# EtherCAT_Sheet.net
KiCad netlist of a schematic drawn in Altium Designer
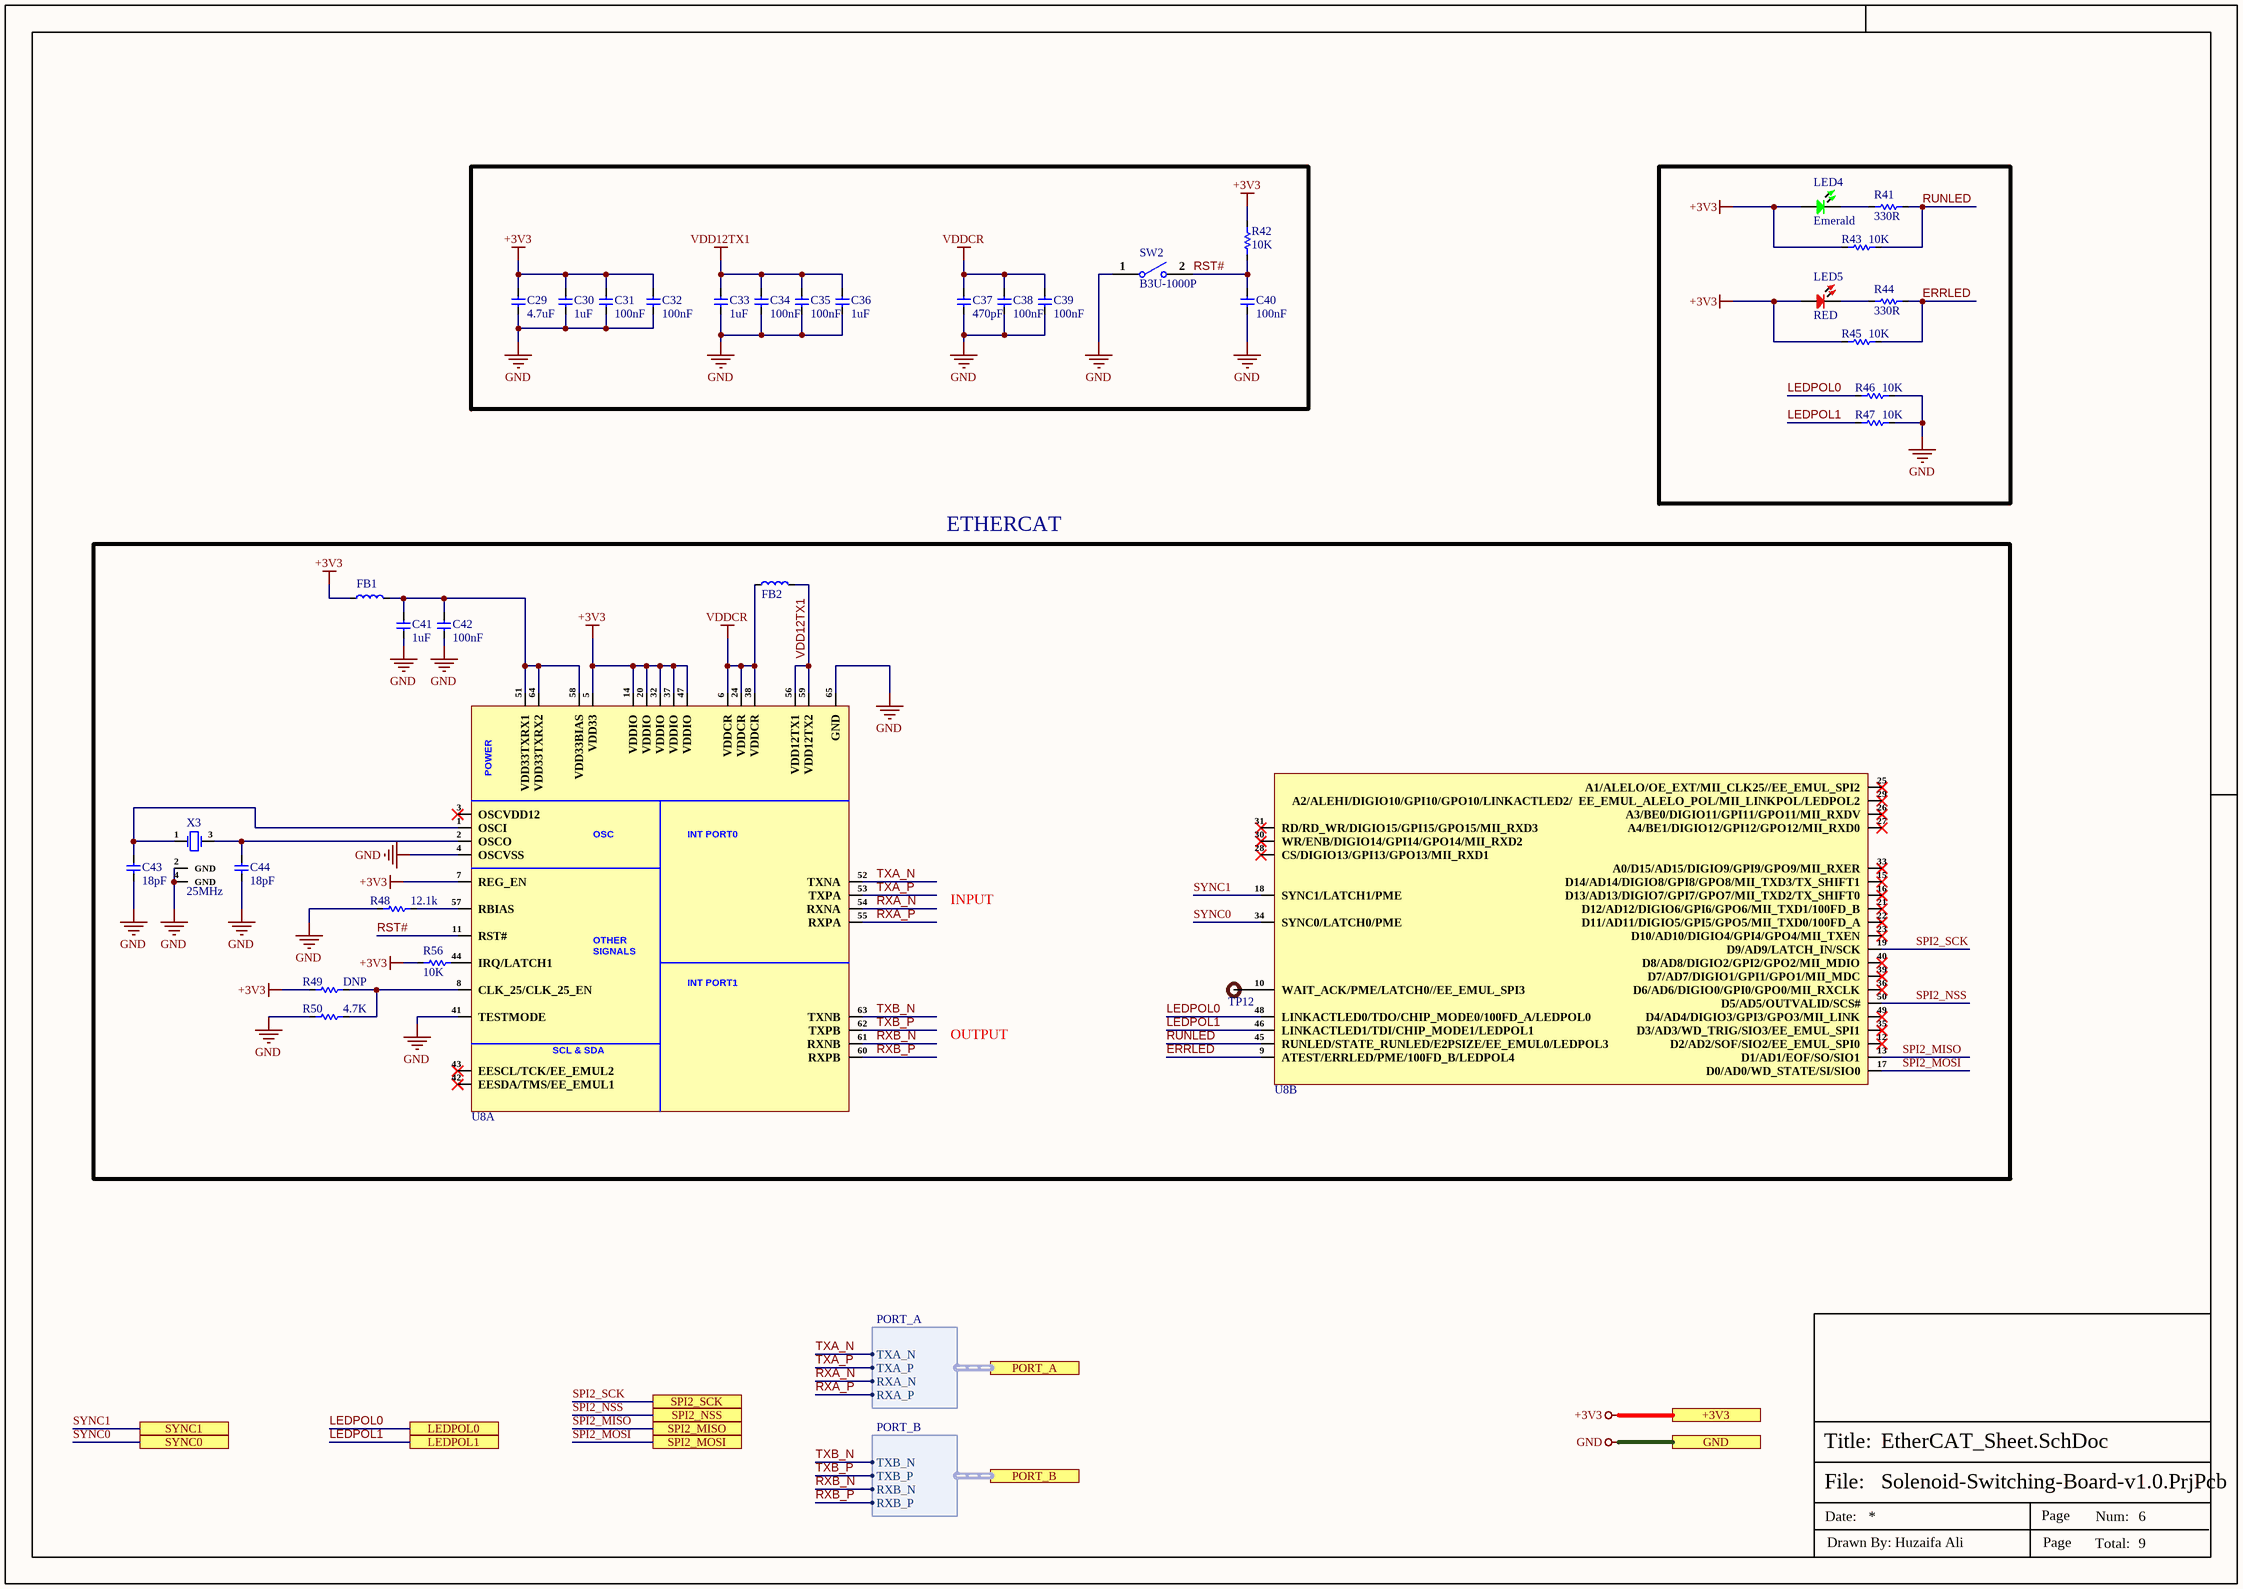
[diagram p0: EtherCAT_Sheet.SchDoc]

(export (version "E")
  (design (tool "Eeschema 10.0.6"))
  (components
    (comp (ref "C29")
      (value "4.7uF")
      (footprint "Cap-0402")
      (description "CAP CER 4.7UF 10V X5R 0402")
      (fields
        (field (name "MANUFACTURER") "Yageo")
        (field (name "MANUFACTURER PART NUMBER") "CC0402KRX5R6BB475")
      )
      (libsource (lib "eSpark Libraries") (part "CC0402KRX5R6BB475"))
    )
    (comp (ref "C30")
      (value "1uF")
      (footprint "Cap-0402")
      (description "CAP CER 1UF 10V X5R 0402")
      (fields
        (field (name "MANUFACTURER") "Yageo")
        (field (name "MANUFACTURER PART NUMBER") "CC0402KRX5R6BB105")
      )
      (libsource (lib "eSpark Libraries") (part "CC0402KRX5R6BB105"))
    )
    (comp (ref "C31")
      (value "100nF")
      (footprint "cap-0402")
      (description "CAP CER 0.1UF 50V X7R 0402")
      (fields
        (field (name "MANUFACTURER") "TDK")
        (field (name "MANUFACTURER PART NUMBER") "C1005X7R1H104KT000F")
      )
      (libsource (lib "eSpark Libraries") (part "C1005X7R1H104KT000F"))
    )
    (comp (ref "C32")
      (value "100nF")
      (footprint "cap-0402")
      (description "CAP CER 0.1UF 50V X7R 0402")
      (fields
        (field (name "MANUFACTURER") "TDK")
        (field (name "MANUFACTURER PART NUMBER") "C1005X7R1H104KT000F")
      )
      (libsource (lib "eSpark Libraries") (part "C1005X7R1H104KT000F"))
    )
    (comp (ref "C33")
      (value "1uF")
      (footprint "Cap-0402")
      (description "CAP CER 1UF 10V X5R 0402")
      (fields
        (field (name "MANUFACTURER") "Yageo")
        (field (name "MANUFACTURER PART NUMBER") "CC0402KRX5R6BB105")
      )
      (libsource (lib "eSpark Libraries") (part "CC0402KRX5R6BB105"))
    )
    (comp (ref "C34")
      (value "100nF")
      (footprint "cap-0402")
      (description "CAP CER 0.1UF 50V X7R 0402")
      (fields
        (field (name "MANUFACTURER") "TDK")
        (field (name "MANUFACTURER PART NUMBER") "C1005X7R1H104KT000F")
      )
      (libsource (lib "eSpark Libraries") (part "C1005X7R1H104KT000F"))
    )
    (comp (ref "C35")
      (value "100nF")
      (footprint "cap-0402")
      (description "CAP CER 0.1UF 50V X7R 0402")
      (fields
        (field (name "MANUFACTURER") "TDK")
        (field (name "MANUFACTURER PART NUMBER") "C1005X7R1H104KT000F")
      )
      (libsource (lib "eSpark Libraries") (part "C1005X7R1H104KT000F"))
    )
    (comp (ref "C36")
      (value "1uF")
      (footprint "Cap-0402")
      (description "CAP CER 1UF 10V X5R 0402")
      (fields
        (field (name "MANUFACTURER") "Yageo")
        (field (name "MANUFACTURER PART NUMBER") "CC0402KRX5R6BB105")
      )
      (libsource (lib "eSpark Libraries") (part "CC0402KRX5R6BB105"))
    )
    (comp (ref "C37")
      (value "470pF")
      (footprint "Cap-0603")
      (description "CAP CER 470PF 50V X7R 0603")
      (fields
        (field (name "MANUFACTURER") "Walsin Technologies")
        (field (name "MANUFACTURER PART NUMBER") "0603B471K500CT")
      )
      (libsource (lib "eSpark Libraries") (part "0603B471K500CT"))
    )
    (comp (ref "C38")
      (value "100nF")
      (footprint "cap-0402")
      (description "CAP CER 0.1UF 50V X7R 0402")
      (fields
        (field (name "MANUFACTURER") "TDK")
        (field (name "MANUFACTURER PART NUMBER") "C1005X7R1H104KT000F")
      )
      (libsource (lib "eSpark Libraries") (part "C1005X7R1H104KT000F"))
    )
    (comp (ref "C39")
      (value "100nF")
      (footprint "cap-0402")
      (description "CAP CER 0.1UF 50V X7R 0402")
      (fields
        (field (name "MANUFACTURER") "TDK")
        (field (name "MANUFACTURER PART NUMBER") "C1005X7R1H104KT000F")
      )
      (libsource (lib "eSpark Libraries") (part "C1005X7R1H104KT000F"))
    )
    (comp (ref "C40")
      (value "100nF")
      (footprint "cap-0402")
      (description "CAP CER 0.1UF 50V X7R 0402")
      (fields
        (field (name "MANUFACTURER") "TDK")
        (field (name "MANUFACTURER PART NUMBER") "C1005X7R1H104KT000F")
      )
      (libsource (lib "eSpark Libraries") (part "C1005X7R1H104KT000F"))
    )
    (comp (ref "C41")
      (value "1uF")
      (footprint "Cap-0402")
      (description "CAP CER 1UF 10V X5R 0402")
      (fields
        (field (name "MANUFACTURER") "Yageo")
        (field (name "MANUFACTURER PART NUMBER") "CC0402KRX5R6BB105")
      )
      (libsource (lib "eSpark Libraries") (part "CC0402KRX5R6BB105"))
    )
    (comp (ref "C42")
      (value "100nF")
      (footprint "cap-0402")
      (description "CAP CER 0.1UF 50V X7R 0402")
      (fields
        (field (name "MANUFACTURER") "TDK")
        (field (name "MANUFACTURER PART NUMBER") "C1005X7R1H104KT000F")
      )
      (libsource (lib "eSpark Libraries") (part "C1005X7R1H104KT000F"))
    )
    (comp (ref "C43")
      (value "18pF")
      (footprint "Cap-0402")
      (description "CAP CER 18PF 50V C0G/NP0 0402")
      (fields
        (field (name "MANUFACTURER") "Murata")
        (field (name "MANUFACTURER PART NUMBER") "GCM1555C1H180GA16D")
      )
      (libsource (lib "eSpark Libraries") (part "GCM1555C1H180GA16D"))
    )
    (comp (ref "C44")
      (value "18pF")
      (footprint "Cap-0402")
      (description "CAP CER 18PF 50V C0G/NP0 0402")
      (fields
        (field (name "MANUFACTURER") "Murata")
        (field (name "MANUFACTURER PART NUMBER") "GCM1555C1H180GA16D")
      )
      (libsource (lib "eSpark Libraries") (part "GCM1555C1H180GA16D"))
    )
    (comp (ref "FB1")
      (value "BLM15PG100SN1D")
      (footprint "IND-0402")
      (description "FERRITE BEAD 10 OHM 0402 1LN")
      (fields (field (name "MANUFACTURER") "Murata") (field (name "TOLERANCE") "25%"))
      (libsource (lib "eSpark Libraries") (part "BLM15PG100SN1D"))
    )
    (comp (ref "FB2")
      (value "BLM15PG100SN1D")
      (footprint "IND-0402")
      (description "FERRITE BEAD 10 OHM 0402 1LN")
      (fields (field (name "MANUFACTURER") "Murata") (field (name "TOLERANCE") "25%"))
      (libsource (lib "eSpark Libraries") (part "BLM15PG100SN1D"))
    )
    (comp (ref "LED4")
      (value "Emerald")
      (footprint "LED-0603")
      (description "Emerald 0603 Light Emitting Diodes (LED) ROHS")
      (fields
        (field (name "MANUFACTURER") "Foshan NationStar Optoelectronics")
        (field (name "MANUFACTURER PART NUMBER") "NCD0603G2")
      )
      (libsource (lib "eSpark Libraries") (part "NCD0603G2"))
    )
    (comp (ref "LED5")
      (value "RED")
      (footprint "LED-0603")
      (description "RED LED 0603 Light Emitting Diodes")
      (fields
        (field (name "MANUFACTURER") "Foshan NationStar Optoelectronics")
        (field (name "MANUFACTURER PART NUMBER") "NCD0603R3")
      )
      (libsource (lib "eSpark Libraries") (part "NCD0603R3"))
    )
    (comp (ref "R41")
      (value "330R")
      (footprint "Res-0603")
      (description "RES  SMD 330R 100 mW 0603")
      (fields
        (field (name "MANUFACTURER") "Yageo")
        (field (name "MANUFACTURER PART NUMBER") "RC0603JR-07330RL")
      )
      (libsource (lib "eSpark Libraries") (part "RC0603JR-07330RL"))
    )
    (comp (ref "R42")
      (value "10K")
      (footprint "Res-0402")
      (description "RES 10K OHM 1% 1/16W 0402")
      (fields
        (field (name "MANUFACTURER") "Yageo")
        (field (name "MANUFACTURER PART NUMBER") "RC0402FR-0710KL")
      )
      (libsource (lib "eSpark Libraries") (part "RC0402FR-0710KL"))
    )
    (comp (ref "R43")
      (value "10K")
      (footprint "Res-0402")
      (description "RES 10K OHM 1% 1/16W 0402")
      (fields
        (field (name "MANUFACTURER") "Yageo")
        (field (name "MANUFACTURER PART NUMBER") "RC0402FR-0710KL")
      )
      (libsource (lib "eSpark Libraries") (part "RC0402FR-0710KL"))
    )
    (comp (ref "R44")
      (value "330R")
      (footprint "Res-0603")
      (description "RES  SMD 330R 100 mW 0603")
      (fields
        (field (name "MANUFACTURER") "Yageo")
        (field (name "MANUFACTURER PART NUMBER") "RC0603JR-07330RL")
      )
      (libsource (lib "eSpark Libraries") (part "RC0603JR-07330RL"))
    )
    (comp (ref "R45")
      (value "10K")
      (footprint "Res-0402")
      (description "RES 10K OHM 1% 1/16W 0402")
      (fields
        (field (name "MANUFACTURER") "Yageo")
        (field (name "MANUFACTURER PART NUMBER") "RC0402FR-0710KL")
      )
      (libsource (lib "eSpark Libraries") (part "RC0402FR-0710KL"))
    )
    (comp (ref "R46")
      (value "10K")
      (footprint "Res-0402")
      (description "RES 10K OHM 1% 1/16W 0402")
      (fields
        (field (name "MANUFACTURER") "Yageo")
        (field (name "MANUFACTURER PART NUMBER") "RC0402FR-0710KL")
      )
      (libsource (lib "eSpark Libraries") (part "RC0402FR-0710KL"))
    )
    (comp (ref "R47")
      (value "10K")
      (footprint "Res-0402")
      (description "RES 10K OHM 1% 1/16W 0402")
      (fields
        (field (name "MANUFACTURER") "Yageo")
        (field (name "MANUFACTURER PART NUMBER") "RC0402FR-0710KL")
      )
      (libsource (lib "eSpark Libraries") (part "RC0402FR-0710KL"))
    )
    (comp (ref "R48")
      (value "12.1k")
      (footprint "Res-0402")
      (description "RES SMD 12.1KOHM 0.1% 1/16W 0402")
      (fields
        (field (name "MANUFACTURER") "Yageo")
        (field (name "MANUFACTURER PART NUMBER") "RT0402BRD0712K1L")
      )
      (libsource (lib "eSpark Libraries") (part "RT0402BRD0712K1L"))
    )
    (comp (ref "R49")
      (value "DNP")
      (footprint "Res-0402")
      (description "RES 4.7K OHM 1% 1/16W 0402")
      (fields
        (field (name "MANUFACTURER") "Yageo")
        (field (name "MANUFACTURER PART NUMBER") "RC0402FR-074K7L")
      )
      (libsource (lib "eSpark Libraries") (part "RC0402FR-074K7L"))
    )
    (comp (ref "R50")
      (value "4.7K")
      (footprint "Res-0402")
      (description "RES 4.7K OHM 1% 1/16W 0402")
      (fields
        (field (name "MANUFACTURER") "Yageo")
        (field (name "MANUFACTURER PART NUMBER") "RC0402FR-074K7L")
      )
      (libsource (lib "eSpark Libraries") (part "RC0402FR-074K7L"))
    )
    (comp (ref "R56")
      (value "10K")
      (footprint "Res-0402")
      (description "RES 10K OHM 1% 1/16W 0402")
      (fields
        (field (name "MANUFACTURER") "Yageo")
        (field (name "MANUFACTURER PART NUMBER") "RC0402FR-0710KL")
      )
      (libsource (lib "eSpark Libraries") (part "RC0402FR-0710KL"))
    )
    (comp (ref "SW2")
      (value "B3U-1000P")
      (footprint "B3U-1000P")
      (description "SWITCH TACTILE SPST-NO 0.05A 12V")
      (fields (field (name "MANUFACTURER") "Omron") (field (name "LCSC PART NUMBER") "C231329"))
      (libsource (lib "eSpark Libraries") (part "B3U-1000P"))
    )
    (comp (ref "TP12")
      (value "TEST POINT")
      (footprint "Test-point")
      (description "Test Point ON")
      (libsource (lib "eSpark Libraries") (part "TEST POINT"))
    )
    (comp (ref "U8")
      (value "LAN9253-SVB QFN64")
      (footprint "QFN-64-EP(9x9)")
      (description "2/3-PORT ETHERCAT SLAVE CTLR")
      (fields
        (field (name "MANUFACTURER") "Microchip")
        (field (name "MANUFACTURER PART NUMBER") "LAN9253-I/R4X")
      )
      (libsource (lib "eSpark Libraries") (part "LAN9253-SVB QFN64"))
    )
    (comp (ref "X3")
      (value "25MHz")
      (footprint "SMD3225-4P")
      (description "25MHz 贴片晶振 18pF ±10ppm ±20ppm SMD3225-4P Crystals ROHS")
      (fields (field (name "LCSC PART NUMBER") "C70593") (field (name "MANUFACTURER") "YXC"))
      (libsource (lib "eSpark Libraries") (part "X322525MRB4SI"))
    )
  )
  (nets
    (net (code "3") (name "+3V3") (class "Default")
      (node (ref "C29") (pin "2") (pinfunction "2_2") (pintype "passive"))
      (node (ref "C30") (pin "2") (pinfunction "2_2") (pintype "passive"))
      (node (ref "C31") (pin "2") (pinfunction "2_2") (pintype "passive"))
      (node (ref "C32") (pin "2") (pinfunction "2_2") (pintype "passive"))
      (node (ref "FB1") (pin "1") (pinfunction "1_1") (pintype "passive"))
      (node (ref "LED4") (pin "1") (pinfunction "1_1") (pintype "passive"))
      (node (ref "LED5") (pin "1") (pinfunction "1_1") (pintype "passive"))
      (node (ref "R42") (pin "1") (pinfunction "1_1") (pintype "passive"))
      (node (ref "R43") (pin "2") (pinfunction "2_2") (pintype "passive"))
      (node (ref "R45") (pin "2") (pinfunction "2_2") (pintype "passive"))
      (node (ref "R49") (pin "1") (pinfunction "1_1") (pintype "passive"))
      (node (ref "R56") (pin "1") (pinfunction "1_1") (pintype "passive"))
      (node (ref "U8") (pin "14") (pinfunction "VDDIO_14") (pintype "passive"))
      (node (ref "U8") (pin "20") (pinfunction "VDDIO_20") (pintype "passive"))
      (node (ref "U8") (pin "32") (pinfunction "VDDIO_32") (pintype "passive"))
      (node (ref "U8") (pin "37") (pinfunction "VDDIO_37") (pintype "passive"))
      (node (ref "U8") (pin "47") (pinfunction "VDDIO_47") (pintype "passive"))
      (node (ref "U8") (pin "5") (pinfunction "VDD33_5") (pintype "passive"))
      (node (ref "U8") (pin "7") (pinfunction "REG_EN_7") (pintype "passive"))
    )
    (net (code "4") (name "/ERRLED") (class "Default")
      (node (ref "R44") (pin "2") (pinfunction "2_2") (pintype "passive"))
      (node (ref "R45") (pin "1") (pinfunction "1_1") (pintype "passive"))
      (node (ref "U8") (pin "9") (pinfunction "ATEST/ERRLED/PME/100FD_B/LEDPOL4_9") (pintype "passive"))
    )
    (net (code "5") (name "/LEDPOL0") (class "Default")
      (node (ref "R46") (pin "2") (pinfunction "2_2") (pintype "passive"))
      (node (ref "U8") (pin "48") (pinfunction "LINKACTLED0/TDO/CHIP_MODE0/100FD_A/LEDPOL0_48") (pintype "passive"))
    )
    (net (code "6") (name "/LEDPOL1") (class "Default")
      (node (ref "R47") (pin "2") (pinfunction "2_2") (pintype "passive"))
      (node (ref "U8") (pin "46") (pinfunction "LINKACTLED1/TDI/CHIP_MODE1/LEDPOL1_46") (pintype "passive"))
    )
    (net (code "7") (name "/RST#") (class "Default")
      (node (ref "C40") (pin "2") (pinfunction "2_2") (pintype "passive"))
      (node (ref "R42") (pin "2") (pinfunction "2_2") (pintype "passive"))
      (node (ref "SW2") (pin "2") (pinfunction "2_2") (pintype "passive"))
      (node (ref "U8") (pin "11") (pinfunction "RST#_11") (pintype "passive"))
    )
    (net (code "8") (name "/RUNLED") (class "Default")
      (node (ref "R41") (pin "2") (pinfunction "2_2") (pintype "passive"))
      (node (ref "R43") (pin "1") (pinfunction "1_1") (pintype "passive"))
      (node (ref "U8") (pin "45") (pinfunction "RUNLED/STATE_RUNLED/E2PSIZE/EE_EMUL0/LEDPOL3_45") (pintype "passive"))
    )
    (net (code "9") (name "/RXA_N") (class "Default")
      (node (ref "U8") (pin "54") (pinfunction "RXNA_54") (pintype "passive"))
    )
    (net (code "10") (name "/RXA_P") (class "Default")
      (node (ref "U8") (pin "55") (pinfunction "RXPA_55") (pintype "passive"))
    )
    (net (code "11") (name "/RXB_N") (class "Default")
      (node (ref "U8") (pin "61") (pinfunction "RXNB_61") (pintype "passive"))
    )
    (net (code "12") (name "/RXB_P") (class "Default")
      (node (ref "U8") (pin "60") (pinfunction "RXPB_60") (pintype "passive"))
    )
    (net (code "13") (name "/SPI2_MISO") (class "Default")
      (node (ref "U8") (pin "13") (pinfunction "D1/AD1/EOF/SO/SIO1_13") (pintype "passive"))
    )
    (net (code "14") (name "/SPI2_MOSI") (class "Default")
      (node (ref "U8") (pin "17") (pinfunction "D0/AD0/WD_STATE/SI/SIO0_17") (pintype "passive"))
    )
    (net (code "15") (name "/SPI2_NSS") (class "Default")
      (node (ref "U8") (pin "50") (pinfunction "D5/AD5/OUTVALID/SCS#_50") (pintype "passive"))
    )
    (net (code "16") (name "/SPI2_SCK") (class "Default")
      (node (ref "U8") (pin "19") (pinfunction "D9/AD9/LATCH_IN/SCK_19") (pintype "passive"))
    )
    (net (code "17") (name "/SYNC0") (class "Default")
      (node (ref "U8") (pin "34") (pinfunction "SYNC0/LATCH0/PME_34") (pintype "passive"))
    )
    (net (code "18") (name "/SYNC1") (class "Default")
      (node (ref "U8") (pin "18") (pinfunction "SYNC1/LATCH1/PME_18") (pintype "passive"))
    )
    (net (code "19") (name "/TXA_N") (class "Default")
      (node (ref "U8") (pin "52") (pinfunction "TXNA_52") (pintype "passive"))
    )
    (net (code "20") (name "/TXA_P") (class "Default")
      (node (ref "U8") (pin "53") (pinfunction "TXPA_53") (pintype "passive"))
    )
    (net (code "21") (name "/TXB_N") (class "Default")
      (node (ref "U8") (pin "63") (pinfunction "TXNB_63") (pintype "passive"))
    )
    (net (code "22") (name "/TXB_P") (class "Default")
      (node (ref "U8") (pin "62") (pinfunction "TXPB_62") (pintype "passive"))
    )
    (net (code "25") (name "GND") (class "Default")
      (node (ref "C29") (pin "1") (pinfunction "1_1") (pintype "passive"))
      (node (ref "C30") (pin "1") (pinfunction "1_1") (pintype "passive"))
      (node (ref "C31") (pin "1") (pinfunction "1_1") (pintype "passive"))
      (node (ref "C32") (pin "1") (pinfunction "1_1") (pintype "passive"))
      (node (ref "C33") (pin "1") (pinfunction "1_1") (pintype "passive"))
      (node (ref "C34") (pin "1") (pinfunction "1_1") (pintype "passive"))
      (node (ref "C35") (pin "1") (pinfunction "1_1") (pintype "passive"))
      (node (ref "C36") (pin "1") (pinfunction "1_1") (pintype "passive"))
      (node (ref "C37") (pin "1") (pinfunction "1_1") (pintype "passive"))
      (node (ref "C38") (pin "1") (pinfunction "1_1") (pintype "passive"))
      (node (ref "C39") (pin "1") (pinfunction "1_1") (pintype "passive"))
      (node (ref "C40") (pin "1") (pinfunction "1_1") (pintype "passive"))
      (node (ref "C41") (pin "1") (pinfunction "1_1") (pintype "passive"))
      (node (ref "C42") (pin "1") (pinfunction "1_1") (pintype "passive"))
      (node (ref "C43") (pin "2") (pinfunction "2_2") (pintype "passive"))
      (node (ref "C44") (pin "2") (pinfunction "2_2") (pintype "passive"))
      (node (ref "R46") (pin "1") (pinfunction "1_1") (pintype "passive"))
      (node (ref "R47") (pin "1") (pinfunction "1_1") (pintype "passive"))
      (node (ref "R48") (pin "1") (pinfunction "1_1") (pintype "passive"))
      (node (ref "R50") (pin "1") (pinfunction "1_1") (pintype "passive"))
      (node (ref "SW2") (pin "1") (pinfunction "1_1") (pintype "passive"))
      (node (ref "U8") (pin "4") (pinfunction "OSCVSS_4") (pintype "passive"))
      (node (ref "U8") (pin "41") (pinfunction "TESTMODE_41") (pintype "passive"))
      (node (ref "U8") (pin "65") (pinfunction "GND_65") (pintype "passive"))
      (node (ref "X3") (pin "2") (pinfunction "GND_2") (pintype "passive"))
      (node (ref "X3") (pin "4") (pinfunction "GND_4") (pintype "passive"))
    )
    (net (code "26") (name "Net-(LED4-Pad2)") (class "Default")
      (node (ref "LED4") (pin "2") (pinfunction "2_2") (pintype "passive"))
      (node (ref "R41") (pin "1") (pinfunction "1_1") (pintype "passive"))
    )
    (net (code "27") (name "Net-(LED5-Pad2)") (class "Default")
      (node (ref "LED5") (pin "2") (pinfunction "2_2") (pintype "passive"))
      (node (ref "R44") (pin "1") (pinfunction "1_1") (pintype "passive"))
    )
    (net (code "28") (name "Net-(U8A-CLK_25{slash}CLK_25_EN)") (class "Default")
      (node (ref "R49") (pin "2") (pinfunction "2_2") (pintype "passive"))
      (node (ref "R50") (pin "2") (pinfunction "2_2") (pintype "passive"))
      (node (ref "U8") (pin "8") (pinfunction "CLK_25/CLK_25_EN_8") (pintype "passive"))
    )
    (net (code "29") (name "Net-(U8A-IRQ{slash}LATCH1)") (class "Default")
      (node (ref "R56") (pin "2") (pinfunction "2_2") (pintype "passive"))
      (node (ref "U8") (pin "44") (pinfunction "IRQ/LATCH1_44") (pintype "passive"))
    )
    (net (code "30") (name "Net-(U8A-OSCI)") (class "Default")
      (node (ref "C43") (pin "1") (pinfunction "1_1") (pintype "passive"))
      (node (ref "U8") (pin "1") (pinfunction "OSCI_1") (pintype "passive"))
      (node (ref "X3") (pin "1") (pinfunction "CRYSTAL_1") (pintype "passive"))
    )
    (net (code "31") (name "Net-(U8A-OSCO)") (class "Default")
      (node (ref "C44") (pin "1") (pinfunction "1_1") (pintype "passive"))
      (node (ref "U8") (pin "2") (pinfunction "OSCO_2") (pintype "passive"))
      (node (ref "X3") (pin "3") (pinfunction "CRYSTAL_3") (pintype "passive"))
    )
    (net (code "32") (name "Net-(U8A-RBIAS)") (class "Default")
      (node (ref "R48") (pin "2") (pinfunction "2_2") (pintype "passive"))
      (node (ref "U8") (pin "57") (pinfunction "RBIAS_57") (pintype "passive"))
    )
    (net (code "33") (name "Net-(U8A-VDD33BIAS)") (class "Default")
      (node (ref "C41") (pin "2") (pinfunction "2_2") (pintype "passive"))
      (node (ref "C42") (pin "2") (pinfunction "2_2") (pintype "passive"))
      (node (ref "FB1") (pin "2") (pinfunction "2_2") (pintype "passive"))
      (node (ref "U8") (pin "51") (pinfunction "VDD33TXRX1_51") (pintype "passive"))
      (node (ref "U8") (pin "58") (pinfunction "VDD33BIAS_58") (pintype "passive"))
      (node (ref "U8") (pin "64") (pinfunction "VDD33TXRX2_64") (pintype "passive"))
    )
    (net (code "34") (name "Net-(U8B-WAIT_ACK{slash}PME{slash}LATCH0{slash}{slash}EE_EMUL_SPI3)") (class "Default")
      (node (ref "TP12") (pin "1") (pinfunction "1_1") (pintype "passive"))
      (node (ref "U8") (pin "10") (pinfunction "WAIT_ACK/PME/LATCH0//EE_EMUL_SPI3_10") (pintype "passive"))
    )
    (net (code "35") (name "VDD12TX1") (class "Default")
      (node (ref "C33") (pin "2") (pinfunction "2_2") (pintype "passive"))
      (node (ref "C34") (pin "2") (pinfunction "2_2") (pintype "passive"))
      (node (ref "C35") (pin "2") (pinfunction "2_2") (pintype "passive"))
      (node (ref "C36") (pin "2") (pinfunction "2_2") (pintype "passive"))
      (node (ref "FB2") (pin "2") (pinfunction "2_2") (pintype "passive"))
      (node (ref "U8") (pin "56") (pinfunction "VDD12TX1_56") (pintype "passive"))
      (node (ref "U8") (pin "59") (pinfunction "VDD12TX2_59") (pintype "passive"))
    )
    (net (code "36") (name "VDDCR") (class "Default")
      (node (ref "C37") (pin "2") (pinfunction "2_2") (pintype "passive"))
      (node (ref "C38") (pin "2") (pinfunction "2_2") (pintype "passive"))
      (node (ref "C39") (pin "2") (pinfunction "2_2") (pintype "passive"))
      (node (ref "FB2") (pin "1") (pinfunction "1_1") (pintype "passive"))
      (node (ref "U8") (pin "24") (pinfunction "VDDCR_24") (pintype "passive"))
      (node (ref "U8") (pin "38") (pinfunction "VDDCR_38") (pintype "passive"))
      (node (ref "U8") (pin "6") (pinfunction "VDDCR_6") (pintype "passive"))
    )
    (net (code "37") (name "unconnected-(U8A-EESCL{slash}TCK{slash}EE_EMUL2-Pad43)") (class "Default")
      (node (ref "U8") (pin "43") (pinfunction "EESCL/TCK/EE_EMUL2_43") (pintype "passive+no_connect"))
    )
    (net (code "38") (name "unconnected-(U8A-EESDA{slash}TMS{slash}EE_EMUL1-Pad42)") (class "Default")
      (node (ref "U8") (pin "42") (pinfunction "EESDA/TMS/EE_EMUL1_42") (pintype "passive+no_connect"))
    )
    (net (code "39") (name "unconnected-(U8A-OSCVDD12-Pad3)") (class "Default")
      (node (ref "U8") (pin "3") (pinfunction "OSCVDD12_3") (pintype "passive+no_connect"))
    )
    (net (code "40") (name "unconnected-(U8B-A0{slash}D15{slash}AD15{slash}DIGIO9{slash}GPI9{slash}GPO9{slash}MII_RXER-Pad33)") (class "Default")
      (node (ref "U8") (pin "33") (pinfunction "A0/D15/AD15/DIGIO9/GPI9/GPO9/MII_RXER_33") (pintype "passive+no_connect"))
    )
    (net (code "41") (name "unconnected-(U8B-A1{slash}ALELO{slash}OE_EXT{slash}MII_CLK25{slash}{slash}EE_EMUL_SPI2-Pad25)") (class "Default")
      (node (ref "U8") (pin "25") (pinfunction "A1/ALELO/OE_EXT/MII_CLK25//EE_EMUL_SPI2_25") (pintype "passive+no_connect"))
    )
    (net (code "42") (name "unconnected-(U8B-A2{slash}ALEHI{slash}DIGIO10{slash}GPI10{slash}GPO10{slash}LINKACTLED2{slash}__EE_EMUL_ALELO_POL{slash}MII_LINKPOL{slash}LEDPOL2-Pad29)") (class "Default")
      (node (ref "U8") (pin "29") (pinfunction "A2/ALEHI/DIGIO10/GPI10/GPO10/LINKACTLED2/__EE_EMUL_ALELO_POL/MII_LINKPOL/LEDPOL2_29") (pintype "passive+no_connect"))
    )
    (net (code "43") (name "unconnected-(U8B-A3{slash}BE0{slash}DIGIO11{slash}GPI11{slash}GPO11{slash}MII_RXDV-Pad26)") (class "Default")
      (node (ref "U8") (pin "26") (pinfunction "A3/BE0/DIGIO11/GPI11/GPO11/MII_RXDV_26") (pintype "passive+no_connect"))
    )
    (net (code "44") (name "unconnected-(U8B-A4{slash}BE1{slash}DIGIO12{slash}GPI12{slash}GPO12{slash}MII_RXD0-Pad27)") (class "Default")
      (node (ref "U8") (pin "27") (pinfunction "A4/BE1/DIGIO12/GPI12/GPO12/MII_RXD0_27") (pintype "passive+no_connect"))
    )
    (net (code "45") (name "unconnected-(U8B-CS{slash}DIGIO13{slash}GPI13{slash}GPO13{slash}MII_RXD1-Pad28)") (class "Default")
      (node (ref "U8") (pin "28") (pinfunction "CS/DIGIO13/GPI13/GPO13/MII_RXD1_28") (pintype "passive+no_connect"))
    )
    (net (code "46") (name "unconnected-(U8B-D2{slash}AD2{slash}SOF{slash}SIO2{slash}EE_EMUL_SPI0-Pad12)") (class "Default")
      (node (ref "U8") (pin "12") (pinfunction "D2/AD2/SOF/SIO2/EE_EMUL_SPI0_12") (pintype "passive+no_connect"))
    )
    (net (code "47") (name "unconnected-(U8B-D3{slash}AD3{slash}WD_TRIG{slash}SIO3{slash}EE_EMUL_SPI1-Pad35)") (class "Default")
      (node (ref "U8") (pin "35") (pinfunction "D3/AD3/WD_TRIG/SIO3/EE_EMUL_SPI1_35") (pintype "passive+no_connect"))
    )
    (net (code "48") (name "unconnected-(U8B-D4{slash}AD4{slash}DIGIO3{slash}GPI3{slash}GPO3{slash}MII_LINK-Pad49)") (class "Default")
      (node (ref "U8") (pin "49") (pinfunction "D4/AD4/DIGIO3/GPI3/GPO3/MII_LINK_49") (pintype "passive+no_connect"))
    )
    (net (code "49") (name "unconnected-(U8B-D6{slash}AD6{slash}DIGIO0{slash}GPI0{slash}GPO0{slash}MII_RXCLK-Pad36)") (class "Default")
      (node (ref "U8") (pin "36") (pinfunction "D6/AD6/DIGIO0/GPI0/GPO0/MII_RXCLK_36") (pintype "passive+no_connect"))
    )
    (net (code "50") (name "unconnected-(U8B-D7{slash}AD7{slash}DIGIO1{slash}GPI1{slash}GPO1{slash}MII_MDC-Pad39)") (class "Default")
      (node (ref "U8") (pin "39") (pinfunction "D7/AD7/DIGIO1/GPI1/GPO1/MII_MDC_39") (pintype "passive+no_connect"))
    )
    (net (code "51") (name "unconnected-(U8B-D8{slash}AD8{slash}DIGIO2{slash}GPI2{slash}GPO2{slash}MII_MDIO-Pad40)") (class "Default")
      (node (ref "U8") (pin "40") (pinfunction "D8/AD8/DIGIO2/GPI2/GPO2/MII_MDIO_40") (pintype "passive+no_connect"))
    )
    (net (code "52") (name "unconnected-(U8B-D10{slash}AD10{slash}DIGIO4{slash}GPI4{slash}GPO4{slash}MII_TXEN-Pad23)") (class "Default")
      (node (ref "U8") (pin "23") (pinfunction "D10/AD10/DIGIO4/GPI4/GPO4/MII_TXEN_23") (pintype "passive+no_connect"))
    )
    (net (code "53") (name "unconnected-(U8B-D11{slash}AD11{slash}DIGIO5{slash}GPI5{slash}GPO5{slash}MII_TXD0{slash}100FD_A-Pad22)") (class "Default")
      (node (ref "U8") (pin "22") (pinfunction "D11/AD11/DIGIO5/GPI5/GPO5/MII_TXD0/100FD_A_22") (pintype "passive+no_connect"))
    )
    (net (code "54") (name "unconnected-(U8B-D12{slash}AD12{slash}DIGIO6{slash}GPI6{slash}GPO6{slash}MII_TXD1{slash}100FD_B-Pad21)") (class "Default")
      (node (ref "U8") (pin "21") (pinfunction "D12/AD12/DIGIO6/GPI6/GPO6/MII_TXD1/100FD_B_21") (pintype "passive+no_connect"))
    )
    (net (code "55") (name "unconnected-(U8B-D13{slash}AD13{slash}DIGIO7{slash}GPI7{slash}GPO7{slash}MII_TXD2{slash}TX_SHIFT0-Pad16)") (class "Default")
      (node (ref "U8") (pin "16") (pinfunction "D13/AD13/DIGIO7/GPI7/GPO7/MII_TXD2/TX_SHIFT0_16") (pintype "passive+no_connect"))
    )
    (net (code "56") (name "unconnected-(U8B-D14{slash}AD14{slash}DIGIO8{slash}GPI8{slash}GPO8{slash}MII_TXD3{slash}TX_SHIFT1-Pad15)") (class "Default")
      (node (ref "U8") (pin "15") (pinfunction "D14/AD14/DIGIO8/GPI8/GPO8/MII_TXD3/TX_SHIFT1_15") (pintype "passive+no_connect"))
    )
    (net (code "57") (name "unconnected-(U8B-RD{slash}RD_WR{slash}DIGIO15{slash}GPI15{slash}GPO15{slash}MII_RXD3-Pad31)") (class "Default")
      (node (ref "U8") (pin "31") (pinfunction "RD/RD_WR/DIGIO15/GPI15/GPO15/MII_RXD3_31") (pintype "passive+no_connect"))
    )
    (net (code "58") (name "unconnected-(U8B-WR{slash}ENB{slash}DIGIO14{slash}GPI14{slash}GPO14{slash}MII_RXD2-Pad30)") (class "Default")
      (node (ref "U8") (pin "30") (pinfunction "WR/ENB/DIGIO14/GPI14/GPO14/MII_RXD2_30") (pintype "passive+no_connect"))
    )
  )
)
